# LCDTFT_FPC40P_SPI4_3p5INCH_RTP.net
KiCad netlist of a schematic drawn in Altium Designer
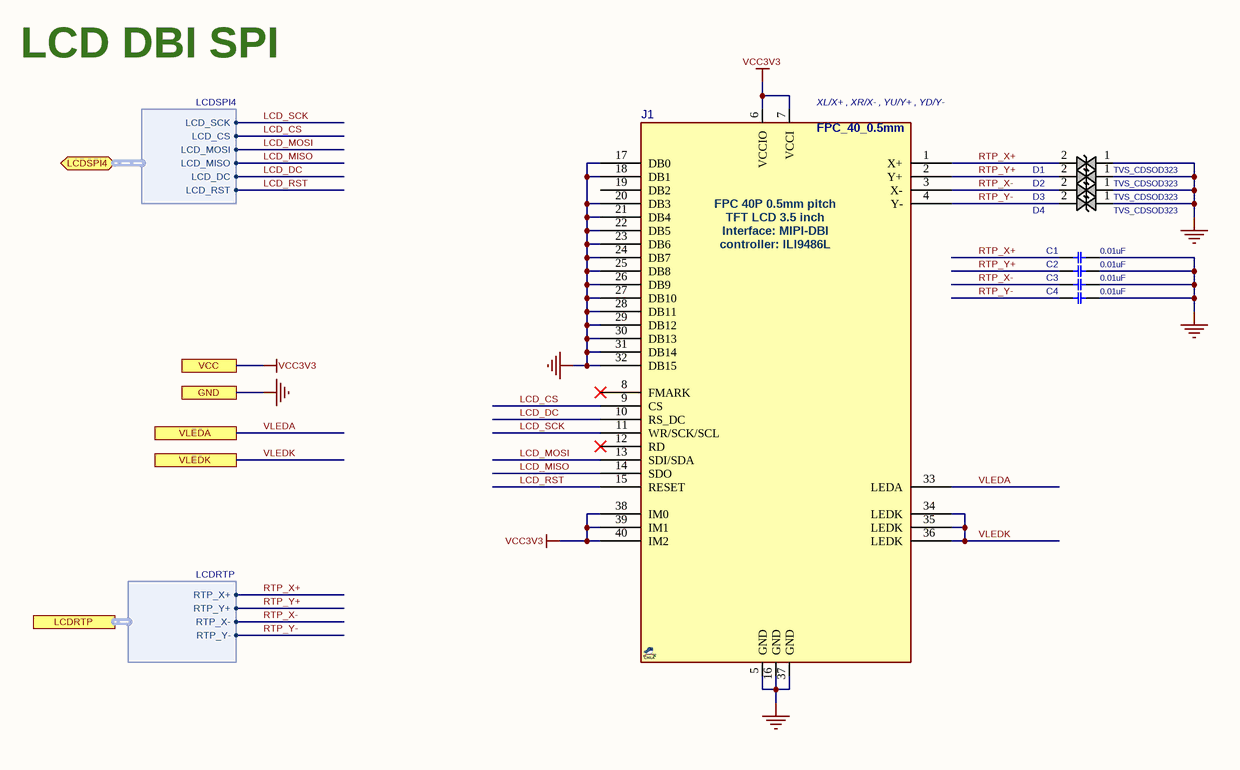
[diagram p0: LCDTFT_FPC40P_SPI4_3p5INCH_RTP.SchDoc]

(export (version "E")
  (design (tool "Eeschema 10.0.6"))
  (components
    (comp (ref "C1")
      (value "0.01uF")
      (footprint "C0402")
      (description "CAP, MLCC")
      (libsource (lib "passive_smd") (part "CAP_SMD_MLCC"))
    )
    (comp (ref "C2")
      (value "0.01uF")
      (footprint "C0402")
      (description "CAP, MLCC")
      (libsource (lib "passive_smd") (part "CAP_SMD_MLCC"))
    )
    (comp (ref "C3")
      (value "0.01uF")
      (footprint "C0402")
      (description "CAP, MLCC")
      (libsource (lib "passive_smd") (part "CAP_SMD_MLCC"))
    )
    (comp (ref "C4")
      (value "0.01uF")
      (footprint "C0402")
      (description "CAP, MLCC")
      (libsource (lib "passive_smd") (part "CAP_SMD_MLCC"))
    )
    (comp (ref "D1")
      (value "TVS_CDSOD323")
      (footprint "D0805")
      (description "TVS, ESD PROTECT, Bidirectional")
      (fields (field (name "MANF_P#") "CDSOD323-T12C") (field (name "MANF") "Bourns"))
      (libsource (lib "protect_tvs_esd_fuse") (part "TVS_CDSOD323"))
    )
    (comp (ref "D2")
      (value "TVS_CDSOD323")
      (footprint "D0805")
      (description "TVS, ESD PROTECT, Bidirectional")
      (fields (field (name "MANF_P#") "CDSOD323-T12C") (field (name "MANF") "Bourns"))
      (libsource (lib "protect_tvs_esd_fuse") (part "TVS_CDSOD323"))
    )
    (comp (ref "D3")
      (value "TVS_CDSOD323")
      (footprint "D0805")
      (description "TVS, ESD PROTECT, Bidirectional")
      (fields (field (name "MANF_P#") "CDSOD323-T12C") (field (name "MANF") "Bourns"))
      (libsource (lib "protect_tvs_esd_fuse") (part "TVS_CDSOD323"))
    )
    (comp (ref "D4")
      (value "TVS_CDSOD323")
      (footprint "D0805")
      (description "TVS, ESD PROTECT, Bidirectional")
      (fields (field (name "MANF_P#") "CDSOD323-T12C") (field (name "MANF") "Bourns"))
      (libsource (lib "protect_tvs_esd_fuse") (part "TVS_CDSOD323"))
    )
    (comp (ref "J1")
      (value "FPC50_40")
      (footprint "FPC50_40T")
      (description "LCD TFT Color, FPC40P, 3.5\" with touch")
      (fields (field (name "MANF") "Hirose") (field (name "MANF_P#") "FH12A-40S-0.5SH"))
      (libsource (lib "lcdtft") (part "LCDTFT_DBI_FPC40P_3.5INCH"))
    )
  )
  (nets
    (net (code "3") (name "/LCD_CS") (class "Default")
      (node (ref "J1") (pin "9") (pinfunction "CS_9") (pintype "passive"))
    )
    (net (code "4") (name "/LCD_DC") (class "Default")
      (node (ref "J1") (pin "10") (pinfunction "RS_DC_10") (pintype "passive"))
    )
    (net (code "5") (name "/LCD_MISO") (class "Default")
      (node (ref "J1") (pin "14") (pinfunction "SDO_14") (pintype "passive"))
    )
    (net (code "6") (name "/LCD_MOSI") (class "Default")
      (node (ref "J1") (pin "13") (pinfunction "SDI/SDA_13") (pintype "passive"))
    )
    (net (code "7") (name "/LCD_RST") (class "Default")
      (node (ref "J1") (pin "15") (pinfunction "RESET_15") (pintype "passive"))
    )
    (net (code "8") (name "/LCD_SCK") (class "Default")
      (node (ref "J1") (pin "11") (pinfunction "WR/SCK/SCL_11") (pintype "passive"))
    )
    (net (code "9") (name "/RTP_X+") (class "Default")
      (node (ref "C1") (pin "2") (pinfunction "2_2") (pintype "passive"))
      (node (ref "D1") (pin "2") (pinfunction "2_2") (pintype "passive"))
      (node (ref "J1") (pin "1") (pinfunction "X+_1") (pintype "passive"))
    )
    (net (code "10") (name "/RTP_X-") (class "Default")
      (node (ref "C3") (pin "2") (pinfunction "2_2") (pintype "passive"))
      (node (ref "D3") (pin "2") (pinfunction "2_2") (pintype "passive"))
      (node (ref "J1") (pin "3") (pinfunction "X-_3") (pintype "passive"))
    )
    (net (code "11") (name "/RTP_Y+") (class "Default")
      (node (ref "C2") (pin "2") (pinfunction "2_2") (pintype "passive"))
      (node (ref "D2") (pin "2") (pinfunction "2_2") (pintype "passive"))
      (node (ref "J1") (pin "2") (pinfunction "Y+_2") (pintype "passive"))
    )
    (net (code "12") (name "/RTP_Y-") (class "Default")
      (node (ref "C4") (pin "2") (pinfunction "2_2") (pintype "passive"))
      (node (ref "D4") (pin "2") (pinfunction "2_2") (pintype "passive"))
      (node (ref "J1") (pin "4") (pinfunction "Y-_4") (pintype "passive"))
    )
    (net (code "13") (name "/VLEDA") (class "Default")
      (node (ref "J1") (pin "33") (pinfunction "LEDA_33") (pintype "passive"))
    )
    (net (code "14") (name "/VLEDK") (class "Default")
      (node (ref "J1") (pin "34") (pinfunction "LEDK_34") (pintype "passive"))
      (node (ref "J1") (pin "35") (pinfunction "LEDK_35") (pintype "passive"))
      (node (ref "J1") (pin "36") (pinfunction "LEDK_36") (pintype "passive"))
    )
    (net (code "17") (name "GND") (class "Default")
      (node (ref "C1") (pin "1") (pinfunction "1_1") (pintype "passive"))
      (node (ref "C2") (pin "1") (pinfunction "1_1") (pintype "passive"))
      (node (ref "C3") (pin "1") (pinfunction "1_1") (pintype "passive"))
      (node (ref "C4") (pin "1") (pinfunction "1_1") (pintype "passive"))
      (node (ref "D1") (pin "1") (pinfunction "1_1") (pintype "passive"))
      (node (ref "D2") (pin "1") (pinfunction "1_1") (pintype "passive"))
      (node (ref "D3") (pin "1") (pinfunction "1_1") (pintype "passive"))
      (node (ref "D4") (pin "1") (pinfunction "1_1") (pintype "passive"))
      (node (ref "J1") (pin "16") (pinfunction "GND_16") (pintype "passive"))
      (node (ref "J1") (pin "17") (pinfunction "DB0_17") (pintype "passive"))
      (node (ref "J1") (pin "18") (pinfunction "DB1_18") (pintype "passive"))
      (node (ref "J1") (pin "20") (pinfunction "DB3_20") (pintype "passive"))
      (node (ref "J1") (pin "21") (pinfunction "DB4_21") (pintype "passive"))
      (node (ref "J1") (pin "22") (pinfunction "DB5_22") (pintype "passive"))
      (node (ref "J1") (pin "23") (pinfunction "DB6_23") (pintype "passive"))
      (node (ref "J1") (pin "24") (pinfunction "DB7_24") (pintype "passive"))
      (node (ref "J1") (pin "25") (pinfunction "DB8_25") (pintype "passive"))
      (node (ref "J1") (pin "26") (pinfunction "DB9_26") (pintype "passive"))
      (node (ref "J1") (pin "27") (pinfunction "DB10_27") (pintype "passive"))
      (node (ref "J1") (pin "28") (pinfunction "DB11_28") (pintype "passive"))
      (node (ref "J1") (pin "29") (pinfunction "DB12_29") (pintype "passive"))
      (node (ref "J1") (pin "30") (pinfunction "DB13_30") (pintype "passive"))
      (node (ref "J1") (pin "31") (pinfunction "DB14_31") (pintype "passive"))
      (node (ref "J1") (pin "32") (pinfunction "DB15_32") (pintype "passive"))
      (node (ref "J1") (pin "37") (pinfunction "GND_37") (pintype "passive"))
      (node (ref "J1") (pin "5") (pinfunction "GND_5") (pintype "passive"))
    )
    (net (code "18") (name "VCC3V3") (class "Default")
      (node (ref "J1") (pin "38") (pinfunction "IM0_38") (pintype "passive"))
      (node (ref "J1") (pin "39") (pinfunction "IM1_39") (pintype "passive"))
      (node (ref "J1") (pin "40") (pinfunction "IM2_40") (pintype "passive"))
      (node (ref "J1") (pin "6") (pinfunction "VCCIO_6") (pintype "passive"))
      (node (ref "J1") (pin "7") (pinfunction "VCCI_7") (pintype "passive"))
    )
    (net (code "19") (name "unconnected-(J1-DB2-Pad19)") (class "Default")
      (node (ref "J1") (pin "19") (pinfunction "DB2_19") (pintype "passive"))
    )
    (net (code "20") (name "unconnected-(J1-FMARK-Pad8)") (class "Default")
      (node (ref "J1") (pin "8") (pinfunction "FMARK_8") (pintype "passive+no_connect"))
    )
    (net (code "21") (name "unconnected-(J1-RD-Pad12)") (class "Default")
      (node (ref "J1") (pin "12") (pinfunction "RD_12") (pintype "passive+no_connect"))
    )
  )
)
